# rf_lpf_17_10.net
KiCad netlist of a schematic drawn in Altium Designer
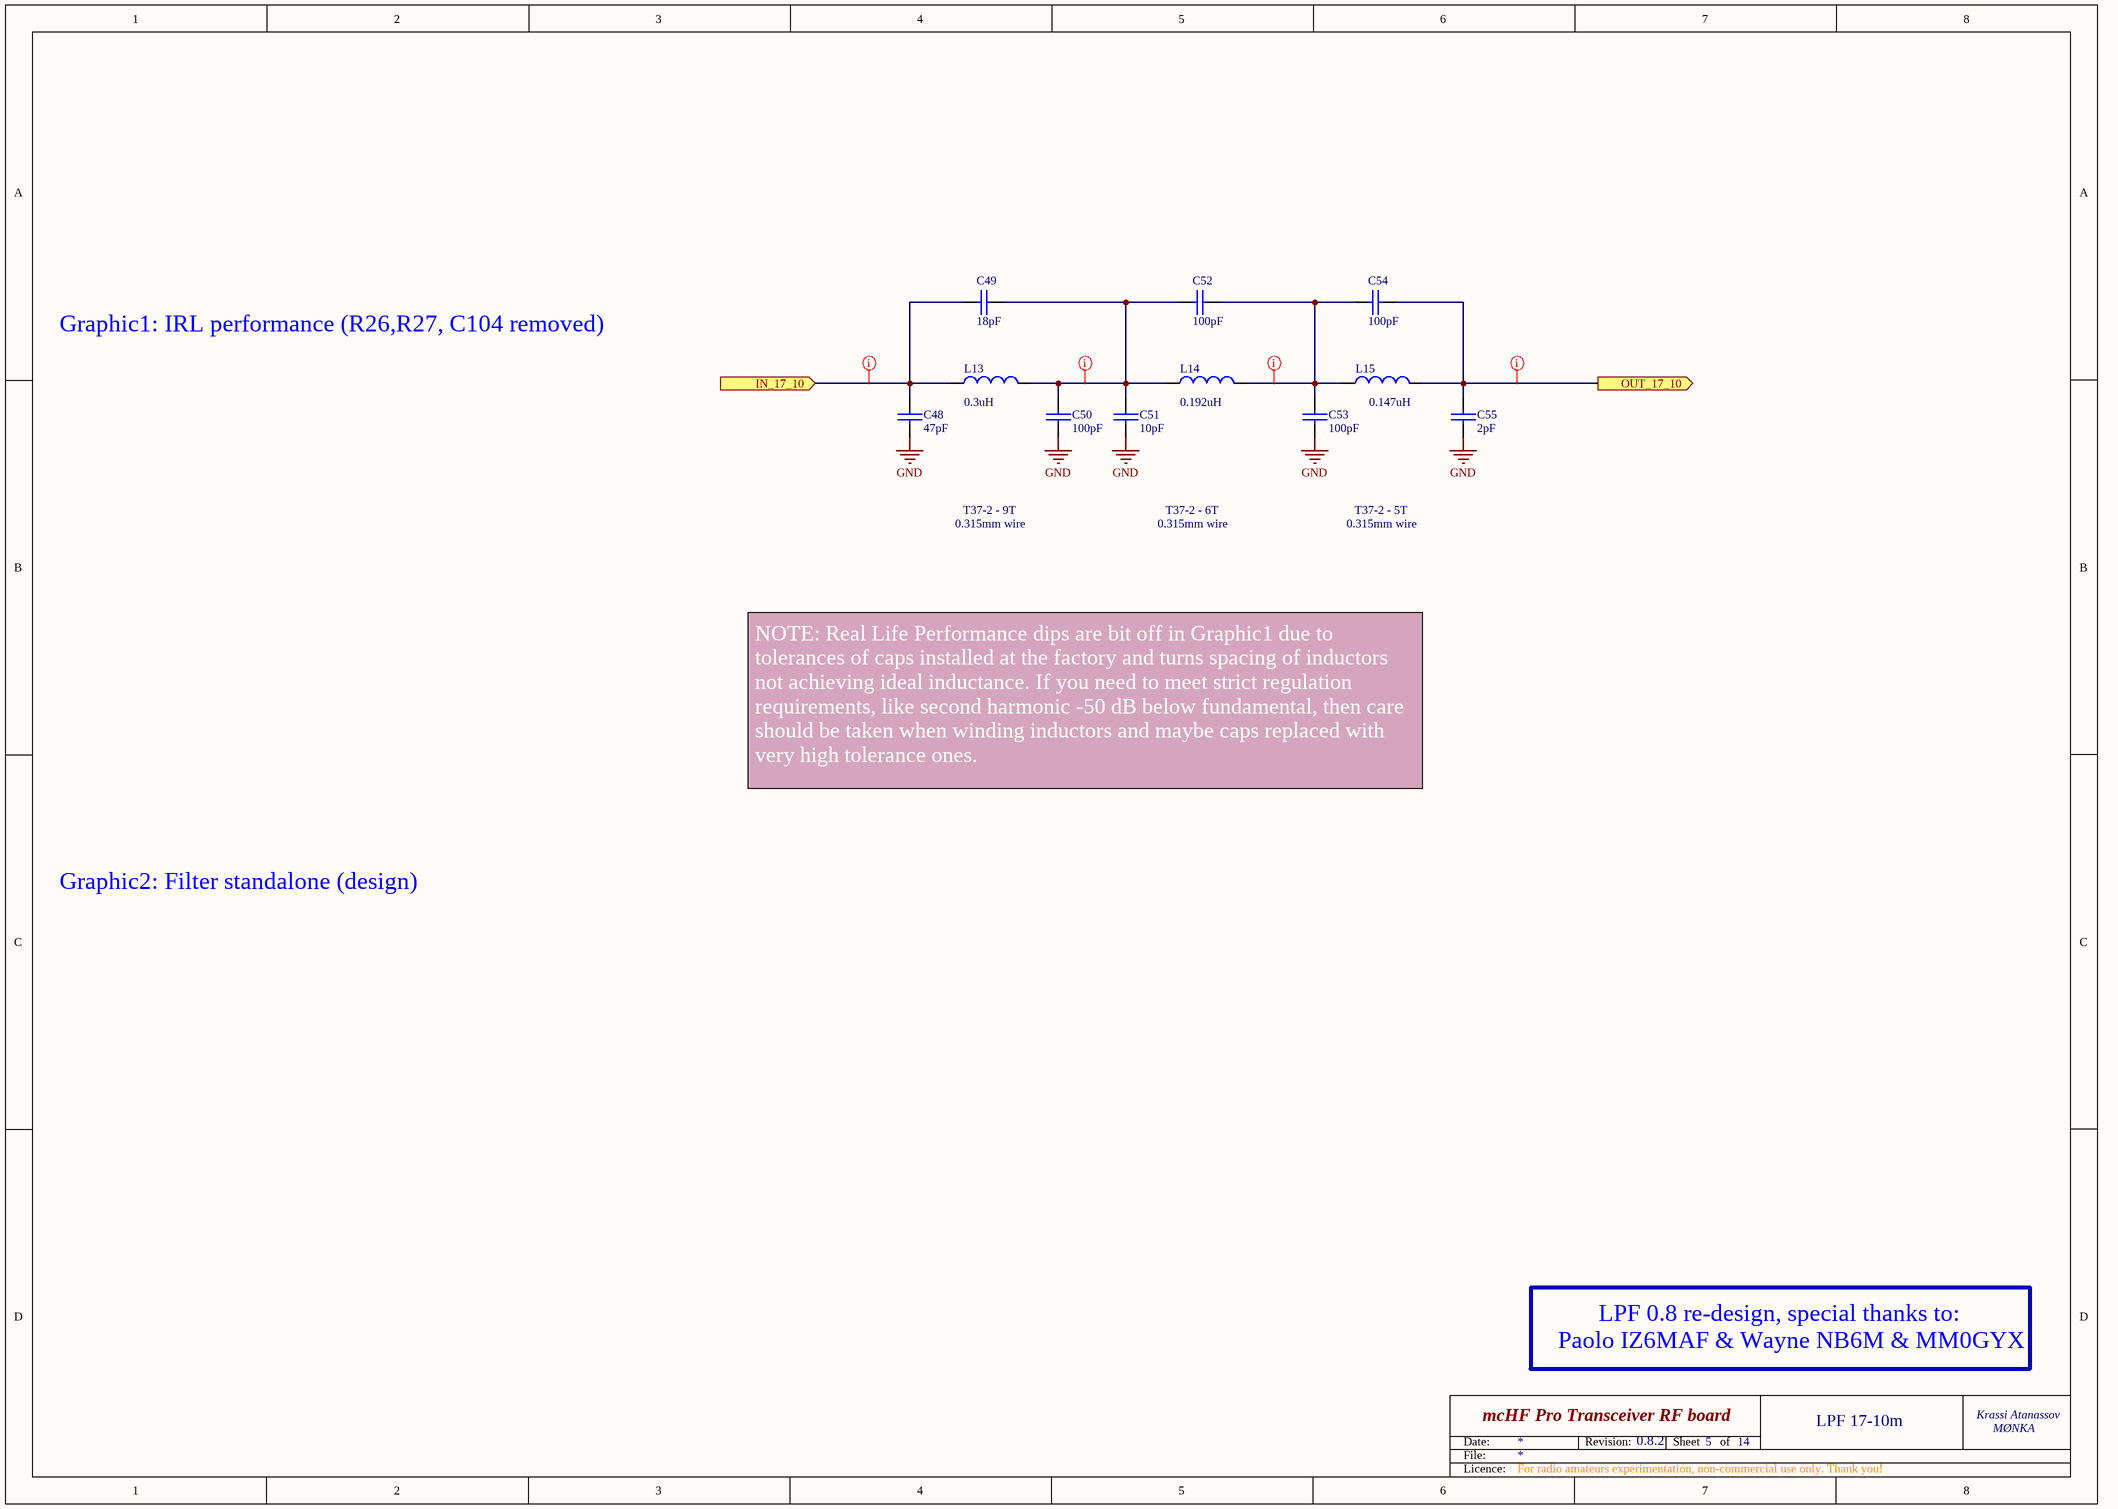
[diagram p0: rf_lpf_17_10.SchDoc]

(export (version "E")
  (design (tool "Eeschema 10.0.6"))
  (components
    (comp (ref "C48")
      (value "47pF")
      (footprint "0805")
      (description "Capacitor")
      (fields (field (name "VOLTAGE") "100V"))
      (libsource (lib "mcHF_rf") (part "CAP"))
    )
    (comp (ref "C49")
      (value "18pF")
      (footprint "0805")
      (description "Capacitor")
      (fields (field (name "VOLTAGE") "100V"))
      (libsource (lib "mcHF_rf") (part "CAP"))
    )
    (comp (ref "C50")
      (value "100pF")
      (footprint "0805")
      (description "Capacitor")
      (fields (field (name "VOLTAGE") "100V"))
      (libsource (lib "mcHF_rf") (part "CAP"))
    )
    (comp (ref "C51")
      (value "10pF")
      (footprint "0805")
      (description "Capacitor")
      (fields (field (name "VOLTAGE") "100V"))
      (libsource (lib "mcHF_rf") (part "CAP"))
    )
    (comp (ref "C52")
      (value "100pF")
      (footprint "0805")
      (description "Capacitor")
      (fields (field (name "VOLTAGE") "100V"))
      (libsource (lib "mcHF_rf") (part "CAP"))
    )
    (comp (ref "C53")
      (value "100pF")
      (footprint "0805")
      (description "Capacitor")
      (fields (field (name "VOLTAGE") "100V"))
      (libsource (lib "mcHF_rf") (part "CAP"))
    )
    (comp (ref "C54")
      (value "100pF")
      (footprint "0805")
      (description "Capacitor")
      (fields (field (name "VOLTAGE") "100V"))
      (libsource (lib "mcHF_rf") (part "CAP"))
    )
    (comp (ref "C55")
      (value "2pF")
      (footprint "0805")
      (description "Capacitor")
      (fields (field (name "VOLTAGE") "100V"))
      (libsource (lib "mcHF_rf") (part "CAP"))
    )
    (comp (ref "L13")
      (value "T37-2")
      (footprint "LPF_IND")
      (description "T37-2 handwound inductor")
      (fields (field (name "INDUCTANCE") "0.3uH"))
      (libsource (lib "mcHF_rf") (part "LPF_IND"))
    )
    (comp (ref "L14")
      (value "T37-2")
      (footprint "LPF_IND")
      (description "T37-2 handwound inductor")
      (fields (field (name "INDUCTANCE") "0.192uH"))
      (libsource (lib "mcHF_rf") (part "LPF_IND"))
    )
    (comp (ref "L15")
      (value "T37-2")
      (footprint "LPF_IND")
      (description "T37-2 handwound inductor")
      (fields (field (name "INDUCTANCE") "0.147uH"))
      (libsource (lib "mcHF_rf") (part "LPF_IND"))
    )
  )
  (nets
    (net (code "1") (name "/IN_17_10") (class "Default")
      (node (ref "C48") (pin "2") (pinfunction "2_2") (pintype "passive"))
      (node (ref "C49") (pin "2") (pinfunction "2_2") (pintype "passive"))
      (node (ref "L13") (pin "1") (pinfunction "1_1") (pintype "passive"))
    )
    (net (code "2") (name "/OUT_17_10") (class "Default")
      (node (ref "C54") (pin "1") (pinfunction "1_1") (pintype "passive"))
      (node (ref "C55") (pin "2") (pinfunction "2_2") (pintype "passive"))
      (node (ref "L15") (pin "2") (pinfunction "2_2") (pintype "passive"))
    )
    (net (code "3") (name "GND") (class "Default")
      (node (ref "C48") (pin "1") (pinfunction "1_1") (pintype "passive"))
      (node (ref "C50") (pin "1") (pinfunction "1_1") (pintype "passive"))
      (node (ref "C51") (pin "1") (pinfunction "1_1") (pintype "passive"))
      (node (ref "C53") (pin "1") (pinfunction "1_1") (pintype "passive"))
      (node (ref "C55") (pin "1") (pinfunction "1_1") (pintype "passive"))
    )
    (net (code "4") (name "Net-(C49-Pad1)") (class "Default")
      (node (ref "C49") (pin "1") (pinfunction "1_1") (pintype "passive"))
      (node (ref "C50") (pin "2") (pinfunction "2_2") (pintype "passive"))
      (node (ref "C51") (pin "2") (pinfunction "2_2") (pintype "passive"))
      (node (ref "C52") (pin "2") (pinfunction "2_2") (pintype "passive"))
      (node (ref "L13") (pin "2") (pinfunction "2_2") (pintype "passive"))
      (node (ref "L14") (pin "1") (pinfunction "1_1") (pintype "passive"))
    )
    (net (code "5") (name "Net-(C52-Pad1)") (class "Default")
      (node (ref "C52") (pin "1") (pinfunction "1_1") (pintype "passive"))
      (node (ref "C53") (pin "2") (pinfunction "2_2") (pintype "passive"))
      (node (ref "C54") (pin "2") (pinfunction "2_2") (pintype "passive"))
      (node (ref "L14") (pin "2") (pinfunction "2_2") (pintype "passive"))
      (node (ref "L15") (pin "1") (pinfunction "1_1") (pintype "passive"))
    )
  )
)
